# LTC6268_circuit.net
KiCad netlist of a schematic drawn in Altium Designer
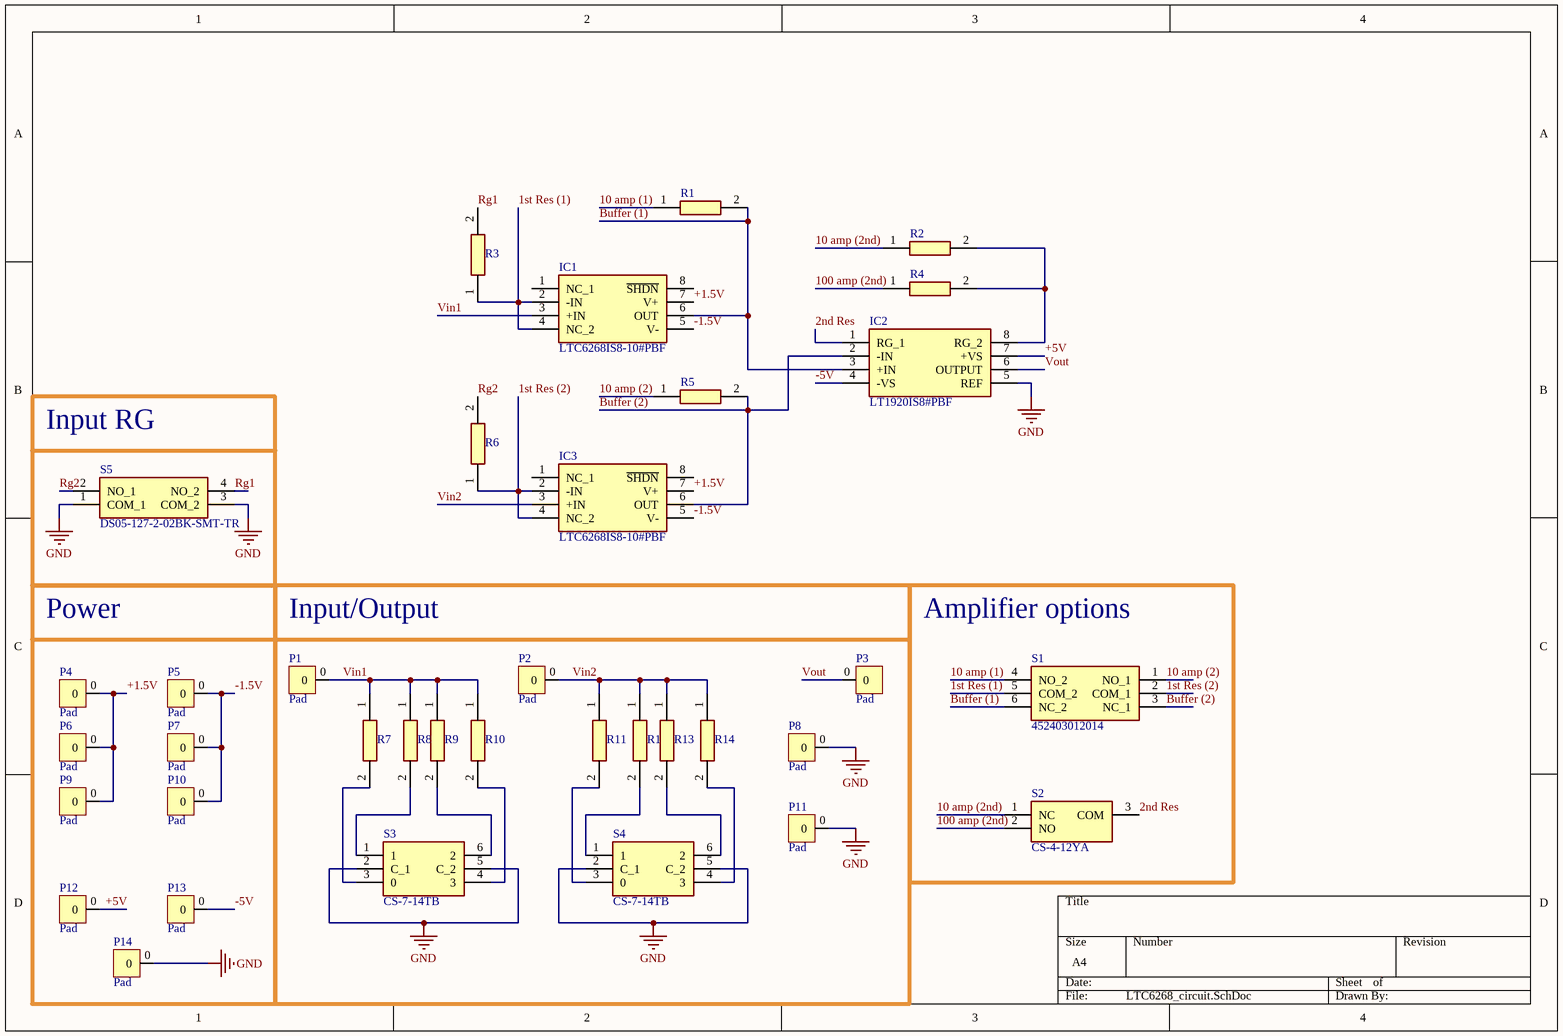
[diagram p0: LTC6268_circuit.SchDoc]

(export (version "E")
  (design (tool "Eeschema 10.0.6"))
  (components
    (comp (ref "IC1")
      (value "LTC6268IS8-10#PBF")
      (footprint "SamacSys:SOIC127P599X175-8N")
      (description "Integrated Circuit")
      (fields (field (name "MOUSER PART NUMBER") "584-LTC6268IS8-10PBF"))
      (libsource (lib "*") (part "LTC6268IS8-10#PBF"))
    )
    (comp (ref "IC2")
      (value "LT1920IS8#PBF")
      (footprint "SamacSys:SOIC127P599X175-8N")
      (description "Integrated Circuit")
      (fields (field (name "MOUSER PART NUMBER") "584-LT1920IS8#PBF"))
      (libsource (lib "SamacSys") (part "LT1920IS8#PBF"))
    )
    (comp (ref "IC3")
      (value "LTC6268IS8-10#PBF")
      (footprint "SamacSys:SOIC127P599X175-8N")
      (description "Integrated Circuit")
      (fields (field (name "MOUSER PART NUMBER") "584-LTC6268IS8-10PBF"))
      (libsource (lib "*") (part "LTC6268IS8-10#PBF"))
    )
    (comp (ref "P1") (value "Pad") (footprint "Pad") (libsource (lib "SamacSys") (part "Pad")))
    (comp (ref "P2") (value "Pad") (footprint "Pad") (libsource (lib "SamacSys") (part "Pad")))
    (comp (ref "P3") (value "Pad") (footprint "Pad") (libsource (lib "") (part "Pad_1")))
    (comp (ref "P4") (value "Pad") (footprint "Pad") (libsource (lib "SamacSys") (part "Pad")))
    (comp (ref "P5") (value "Pad") (footprint "Pad") (libsource (lib "SamacSys") (part "Pad")))
    (comp (ref "P6") (value "Pad") (footprint "Pad") (libsource (lib "SamacSys") (part "Pad")))
    (comp (ref "P7") (value "Pad") (footprint "Pad") (libsource (lib "SamacSys") (part "Pad")))
    (comp (ref "P8") (value "Pad") (footprint "Pad") (libsource (lib "SamacSys") (part "Pad")))
    (comp (ref "P9") (value "Pad") (footprint "Pad") (libsource (lib "SamacSys") (part "Pad")))
    (comp (ref "P10") (value "Pad") (footprint "Pad") (libsource (lib "SamacSys") (part "Pad")))
    (comp (ref "P11") (value "Pad") (footprint "Pad") (libsource (lib "SamacSys") (part "Pad")))
    (comp (ref "P12") (value "Pad") (footprint "Pad") (libsource (lib "SamacSys") (part "Pad")))
    (comp (ref "P13") (value "Pad") (footprint "Pad") (libsource (lib "SamacSys") (part "Pad")))
    (comp (ref "P14") (value "Pad") (footprint "Pad") (libsource (lib "SamacSys") (part "Pad")))
    (comp (ref "R1")
      (value "CRG0805F270R")
      (footprint "SamacSys:RESC2012X65N")
      (description "Resistor 270")
      (fields (field (name "MOUSER PART NUMBER") "279-CRG0805F270R"))
      (libsource (lib "SamacSys") (part "CRG0805F270R"))
    )
    (comp (ref "R2")
      (value "CRG0805F4K7")
      (footprint "SamacSys:RESC2012X65N")
      (description "Resistor 4.7k")
      (fields (field (name "MOUSER PART NUMBER") "279-CRG0805F4K7"))
      (libsource (lib "SamacSys") (part "CRG0805F4K7"))
    )
    (comp (ref "R3")
      (value "CRGH0805F20R")
      (footprint "SamacSys:RESC2013X65N")
      (description "Resistor 20")
      (fields (field (name "MOUSER PART NUMBER") "279-CRGH0805F20R"))
      (libsource (lib "SamacSys") (part "CRGH0805F20R"))
    )
    (comp (ref "R4")
      (value "CRG0805F330R")
      (footprint "SamacSys:RESC2012X65N")
      (description "Resistor 330")
      (fields (field (name "MOUSER PART NUMBER") "279-CRG0805F330R"))
      (libsource (lib "SamacSys") (part "CRG0805F330R"))
    )
    (comp (ref "R5")
      (value "CRG0805F270R")
      (footprint "SamacSys:RESC2012X65N")
      (description "Resistor 270")
      (fields (field (name "MOUSER PART NUMBER") "279-CRG0805F270R"))
      (libsource (lib "SamacSys") (part "CRG0805F270R"))
    )
    (comp (ref "R6")
      (value "CRGH0805F20R")
      (footprint "SamacSys:RESC2013X65N")
      (description "Resistor 20")
      (fields (field (name "MOUSER PART NUMBER") "279-CRGH0805F20R"))
      (libsource (lib "SamacSys") (part "CRGH0805F20R"))
    )
    (comp (ref "R7")
      (value "~")
      (footprint "SamacSys:RESC2013X50N")
      (description "Resistor")
      (fields
        (field (name "MANUFACTURER_PART_NUMBER") "RH73X2A10GNTN")
        (field (name "MOUSER PART NUMBER") "279-RH73X2A10GNTN")
      )
      (libsource (lib "SamacSys") (part "RH73X2A10GNTN"))
    )
    (comp (ref "R8")
      (value "RH73X2A50GNTN")
      (footprint "SamacSys:RESC2013X50N")
      (description "Resistor 50G")
      (fields (field (name "MOUSER PART NUMBER") "279-RH73X2A50GNTN"))
      (libsource (lib "SamacSys") (part "RH73X2A50GNTN"))
    )
    (comp (ref "R9")
      (value "RH73H2A100MKTN")
      (footprint "SamacSys:RESC2013X50N")
      (description "Resistor 100M")
      (fields (field (name "MOUSER PART NUMBER") "279-RH73H2A100MKTN"))
      (libsource (lib "SamacSys") (part "RH73H2A100MKTN"))
    )
    (comp (ref "R10")
      (value "RH73W2A1GNTN")
      (footprint "SamacSys:RESC2013X50N")
      (description "Resistor 1G")
      (fields (field (name "MOUSER PART NUMBER") "279-RH73W2A1GNTN"))
      (libsource (lib "SamacSys") (part "RH73W2A1GNTN"))
    )
    (comp (ref "R11")
      (value "RH73X2A50GNTN")
      (footprint "SamacSys:RESC2013X50N")
      (description "Resistor 50G")
      (fields (field (name "MOUSER PART NUMBER") "279-RH73X2A50GNTN"))
      (libsource (lib "SamacSys") (part "RH73X2A50GNTN"))
    )
    (comp (ref "R12")
      (value "~")
      (footprint "SamacSys:RESC2013X50N")
      (description "Resistor")
      (fields
        (field (name "MANUFACTURER_PART_NUMBER") "RH73X2A10GNTN")
        (field (name "MOUSER PART NUMBER") "279-RH73X2A10GNTN")
      )
      (libsource (lib "SamacSys") (part "RH73X2A10GNTN"))
    )
    (comp (ref "R13")
      (value "RH73W2A1GNTN")
      (footprint "SamacSys:RESC2013X50N")
      (description "Resistor 1G")
      (fields (field (name "MOUSER PART NUMBER") "279-RH73W2A1GNTN"))
      (libsource (lib "SamacSys") (part "RH73W2A1GNTN"))
    )
    (comp (ref "R14")
      (value "RH73H2A100MKTN")
      (footprint "SamacSys:RESC2013X50N")
      (description "Resistor 100M")
      (fields (field (name "MOUSER PART NUMBER") "279-RH73H2A100MKTN"))
      (libsource (lib "SamacSys") (part "RH73H2A100MKTN"))
    )
    (comp (ref "S1")
      (value "452403012014")
      (footprint "SamacSys:452403012014")
      (description "Switch")
      (fields (field (name "MOUSER PART NUMBER") "710-452403012014"))
      (libsource (lib "SamacSys") (part "452403012014"))
    )
    (comp (ref "S2")
      (value "CS-4-12YA")
      (footprint "SamacSys:CS412YA")
      (description "Switch")
      (libsource (lib "SamacSys") (part "CS-4-12YA"))
    )
    (comp (ref "S3")
      (value "CS-7-14TB")
      (footprint "SamacSys:SOP254P1000X405-6N")
      (description "Switch")
      (libsource (lib "*") (part "CS-7-14TB"))
    )
    (comp (ref "S4")
      (value "CS-7-14TB")
      (footprint "SamacSys:SOP254P1000X405-6N")
      (description "Switch")
      (libsource (lib "*") (part "CS-7-14TB"))
    )
    (comp (ref "S5")
      (value "DS05-127-2-02BK-SMT-TR")
      (footprint "SamacSys:DS05127202BKSMTTR")
      (description "Switch")
      (fields (field (name "MOUSER PART NUMBER") "490-DS05127202BK-STR"))
      (libsource (lib "*") (part "DS05-127-2-02BK-SMT-TR"))
    )
  )
  (nets
    (net (code "1") (name "/+1.5V") (class "Default")
      (node (ref "IC1") (pin "7") (pinfunction "V+_7") (pintype "passive"))
      (node (ref "IC3") (pin "7") (pinfunction "V+_7") (pintype "passive"))
      (node (ref "P4") (pin "0") (pinfunction "0_0") (pintype "passive"))
      (node (ref "P6") (pin "0") (pinfunction "0_0") (pintype "passive"))
      (node (ref "P9") (pin "0") (pinfunction "0_0") (pintype "passive"))
    )
    (net (code "2") (name "/+5V") (class "Default")
      (node (ref "IC2") (pin "7") (pinfunction "+VS_7") (pintype "passive"))
      (node (ref "P12") (pin "0") (pinfunction "0_0") (pintype "passive"))
    )
    (net (code "3") (name "/-1.5V") (class "Default")
      (node (ref "IC1") (pin "5") (pinfunction "V-_5") (pintype "passive"))
      (node (ref "IC3") (pin "5") (pinfunction "V-_5") (pintype "passive"))
      (node (ref "P10") (pin "0") (pinfunction "0_0") (pintype "passive"))
      (node (ref "P5") (pin "0") (pinfunction "0_0") (pintype "passive"))
      (node (ref "P7") (pin "0") (pinfunction "0_0") (pintype "passive"))
    )
    (net (code "4") (name "/-5V") (class "Default")
      (node (ref "IC2") (pin "4") (pinfunction "-VS_4") (pintype "passive"))
      (node (ref "P13") (pin "0") (pinfunction "0_0") (pintype "passive"))
    )
    (net (code "5") (name "/1st Res (1)") (class "Default")
      (node (ref "IC1") (pin "2") (pinfunction "-IN_2") (pintype "passive"))
      (node (ref "IC1") (pin "4") (pinfunction "NC_2_4") (pintype "passive"))
      (node (ref "R3") (pin "1") (pinfunction "1_1") (pintype "passive"))
      (node (ref "S1") (pin "5") (pinfunction "COM_2_5") (pintype "passive"))
    )
    (net (code "6") (name "/1st Res (2)") (class "Default")
      (node (ref "IC3") (pin "2") (pinfunction "-IN_2") (pintype "passive"))
      (node (ref "IC3") (pin "4") (pinfunction "NC_2_4") (pintype "passive"))
      (node (ref "R6") (pin "1") (pinfunction "1_1") (pintype "passive"))
      (node (ref "S1") (pin "2") (pinfunction "COM_1_2") (pintype "passive"))
    )
    (net (code "7") (name "/2nd Res") (class "Default")
      (node (ref "IC2") (pin "1") (pinfunction "RG_1_1") (pintype "passive"))
      (node (ref "S2") (pin "3") (pinfunction "COM_3") (pintype "passive"))
    )
    (net (code "8") (name "/10 amp (1)") (class "Default")
      (node (ref "R1") (pin "1") (pinfunction "1_1") (pintype "passive"))
      (node (ref "S1") (pin "4") (pinfunction "NO_2_4") (pintype "passive"))
    )
    (net (code "9") (name "/10 amp (2)") (class "Default")
      (node (ref "R5") (pin "1") (pinfunction "1_1") (pintype "passive"))
      (node (ref "S1") (pin "1") (pinfunction "NO_1_1") (pintype "passive"))
    )
    (net (code "10") (name "/10 amp (2nd)") (class "Default")
      (node (ref "R2") (pin "1") (pinfunction "1_1") (pintype "passive"))
      (node (ref "S2") (pin "1") (pinfunction "NC_1") (pintype "passive"))
    )
    (net (code "11") (name "/100 amp (2nd)") (class "Default")
      (node (ref "R4") (pin "1") (pinfunction "1_1") (pintype "passive"))
      (node (ref "S2") (pin "2") (pinfunction "NO_2") (pintype "passive"))
    )
    (net (code "12") (name "/Buffer (1)") (class "Default")
      (node (ref "IC1") (pin "6") (pinfunction "OUT_6") (pintype "passive"))
      (node (ref "IC2") (pin "3") (pinfunction "+IN_3") (pintype "passive"))
      (node (ref "R1") (pin "2") (pinfunction "2_2") (pintype "passive"))
      (node (ref "S1") (pin "6") (pinfunction "NC_2_6") (pintype "passive"))
    )
    (net (code "13") (name "/Buffer (2)") (class "Default")
      (node (ref "IC2") (pin "2") (pinfunction "-IN_2") (pintype "passive"))
      (node (ref "IC3") (pin "6") (pinfunction "OUT_6") (pintype "passive"))
      (node (ref "R5") (pin "2") (pinfunction "2_2") (pintype "passive"))
      (node (ref "S1") (pin "3") (pinfunction "NC_1_3") (pintype "passive"))
    )
    (net (code "14") (name "/Rg1") (class "Default")
      (node (ref "R3") (pin "2") (pinfunction "2_2") (pintype "passive"))
      (node (ref "S5") (pin "4") (pinfunction "NO_2_4") (pintype "passive"))
    )
    (net (code "15") (name "/Rg2") (class "Default")
      (node (ref "R6") (pin "2") (pinfunction "2_2") (pintype "passive"))
      (node (ref "S5") (pin "2") (pinfunction "NO_1_2") (pintype "passive"))
    )
    (net (code "16") (name "/Vin1") (class "Default")
      (node (ref "IC1") (pin "3") (pinfunction "+IN_3") (pintype "passive"))
      (node (ref "P1") (pin "0") (pinfunction "0_0") (pintype "passive"))
      (node (ref "R10") (pin "1") (pinfunction "1_1") (pintype "passive"))
      (node (ref "R7") (pin "1") (pinfunction "1_1") (pintype "passive"))
      (node (ref "R8") (pin "1") (pinfunction "1_1") (pintype "passive"))
      (node (ref "R9") (pin "1") (pinfunction "1_1") (pintype "passive"))
    )
    (net (code "17") (name "/Vin2") (class "Default")
      (node (ref "IC3") (pin "3") (pinfunction "+IN_3") (pintype "passive"))
      (node (ref "P2") (pin "0") (pinfunction "0_0") (pintype "passive"))
      (node (ref "R11") (pin "1") (pinfunction "1_1") (pintype "passive"))
      (node (ref "R12") (pin "1") (pinfunction "1_1") (pintype "passive"))
      (node (ref "R13") (pin "1") (pinfunction "1_1") (pintype "passive"))
      (node (ref "R14") (pin "1") (pinfunction "1_1") (pintype "passive"))
    )
    (net (code "18") (name "/Vout") (class "Default")
      (node (ref "IC2") (pin "6") (pinfunction "OUTPUT_6") (pintype "passive"))
      (node (ref "P3") (pin "0") (pinfunction "0_0") (pintype "passive"))
    )
    (net (code "19") (name "GND") (class "Default")
      (node (ref "IC2") (pin "5") (pinfunction "REF_5") (pintype "passive"))
      (node (ref "P11") (pin "0") (pinfunction "0_0") (pintype "passive"))
      (node (ref "P14") (pin "0") (pinfunction "0_0") (pintype "passive"))
      (node (ref "P8") (pin "0") (pinfunction "0_0") (pintype "passive"))
      (node (ref "S3") (pin "2") (pinfunction "C_1_2") (pintype "passive"))
      (node (ref "S3") (pin "5") (pinfunction "C_2_5") (pintype "passive"))
      (node (ref "S4") (pin "2") (pinfunction "C_1_2") (pintype "passive"))
      (node (ref "S4") (pin "5") (pinfunction "C_2_5") (pintype "passive"))
      (node (ref "S5") (pin "1") (pinfunction "COM_1_1") (pintype "passive"))
      (node (ref "S5") (pin "3") (pinfunction "COM_2_3") (pintype "passive"))
    )
    (net (code "20") (name "Net-(IC2-RG_2)") (class "Default")
      (node (ref "IC2") (pin "8") (pinfunction "RG_2_8") (pintype "passive"))
      (node (ref "R2") (pin "2") (pinfunction "2_2") (pintype "passive"))
      (node (ref "R4") (pin "2") (pinfunction "2_2") (pintype "passive"))
    )
    (net (code "21") (name "Net-(R8-Pad2)") (class "Default")
      (node (ref "R8") (pin "2") (pinfunction "2_2") (pintype "passive"))
      (node (ref "S3") (pin "1") (pinfunction "1_1") (pintype "passive"))
    )
    (net (code "22") (name "Net-(R12-Pad2)") (class "Default")
      (node (ref "R12") (pin "2") (pinfunction "2_2") (pintype "passive"))
      (node (ref "S4") (pin "1") (pinfunction "1_1") (pintype "passive"))
    )
    (net (code "23") (name "Net-(S3-0)") (class "Default")
      (node (ref "R7") (pin "2") (pinfunction "2_2") (pintype "passive"))
      (node (ref "S3") (pin "3") (pinfunction "0_3") (pintype "passive"))
    )
    (net (code "24") (name "Net-(S3-2)") (class "Default")
      (node (ref "R9") (pin "2") (pinfunction "2_2") (pintype "passive"))
      (node (ref "S3") (pin "6") (pinfunction "2_6") (pintype "passive"))
    )
    (net (code "25") (name "Net-(S3-3)") (class "Default")
      (node (ref "R10") (pin "2") (pinfunction "2_2") (pintype "passive"))
      (node (ref "S3") (pin "4") (pinfunction "3_4") (pintype "passive"))
    )
    (net (code "26") (name "Net-(S4-0)") (class "Default")
      (node (ref "R11") (pin "2") (pinfunction "2_2") (pintype "passive"))
      (node (ref "S4") (pin "3") (pinfunction "0_3") (pintype "passive"))
    )
    (net (code "27") (name "Net-(S4-2)") (class "Default")
      (node (ref "R13") (pin "2") (pinfunction "2_2") (pintype "passive"))
      (node (ref "S4") (pin "6") (pinfunction "2_6") (pintype "passive"))
    )
    (net (code "28") (name "Net-(S4-3)") (class "Default")
      (node (ref "R14") (pin "2") (pinfunction "2_2") (pintype "passive"))
      (node (ref "S4") (pin "4") (pinfunction "3_4") (pintype "passive"))
    )
    (net (code "29") (name "unconnected-(IC1-NC_1-Pad1)") (class "Default")
      (node (ref "IC1") (pin "1") (pinfunction "NC_1_1") (pintype "passive"))
    )
    (net (code "30") (name "unconnected-(IC1-~{SHDN}-Pad8)") (class "Default")
      (node (ref "IC1") (pin "8") (pinfunction "~{SHDN}_8") (pintype "passive"))
    )
    (net (code "31") (name "unconnected-(IC3-NC_1-Pad1)") (class "Default")
      (node (ref "IC3") (pin "1") (pinfunction "NC_1_1") (pintype "passive"))
    )
    (net (code "32") (name "unconnected-(IC3-~{SHDN}-Pad8)") (class "Default")
      (node (ref "IC3") (pin "8") (pinfunction "~{SHDN}_8") (pintype "passive"))
    )
  )
)
